# Carrier_Board.net
KiCad netlist of a schematic drawn in EAGLE
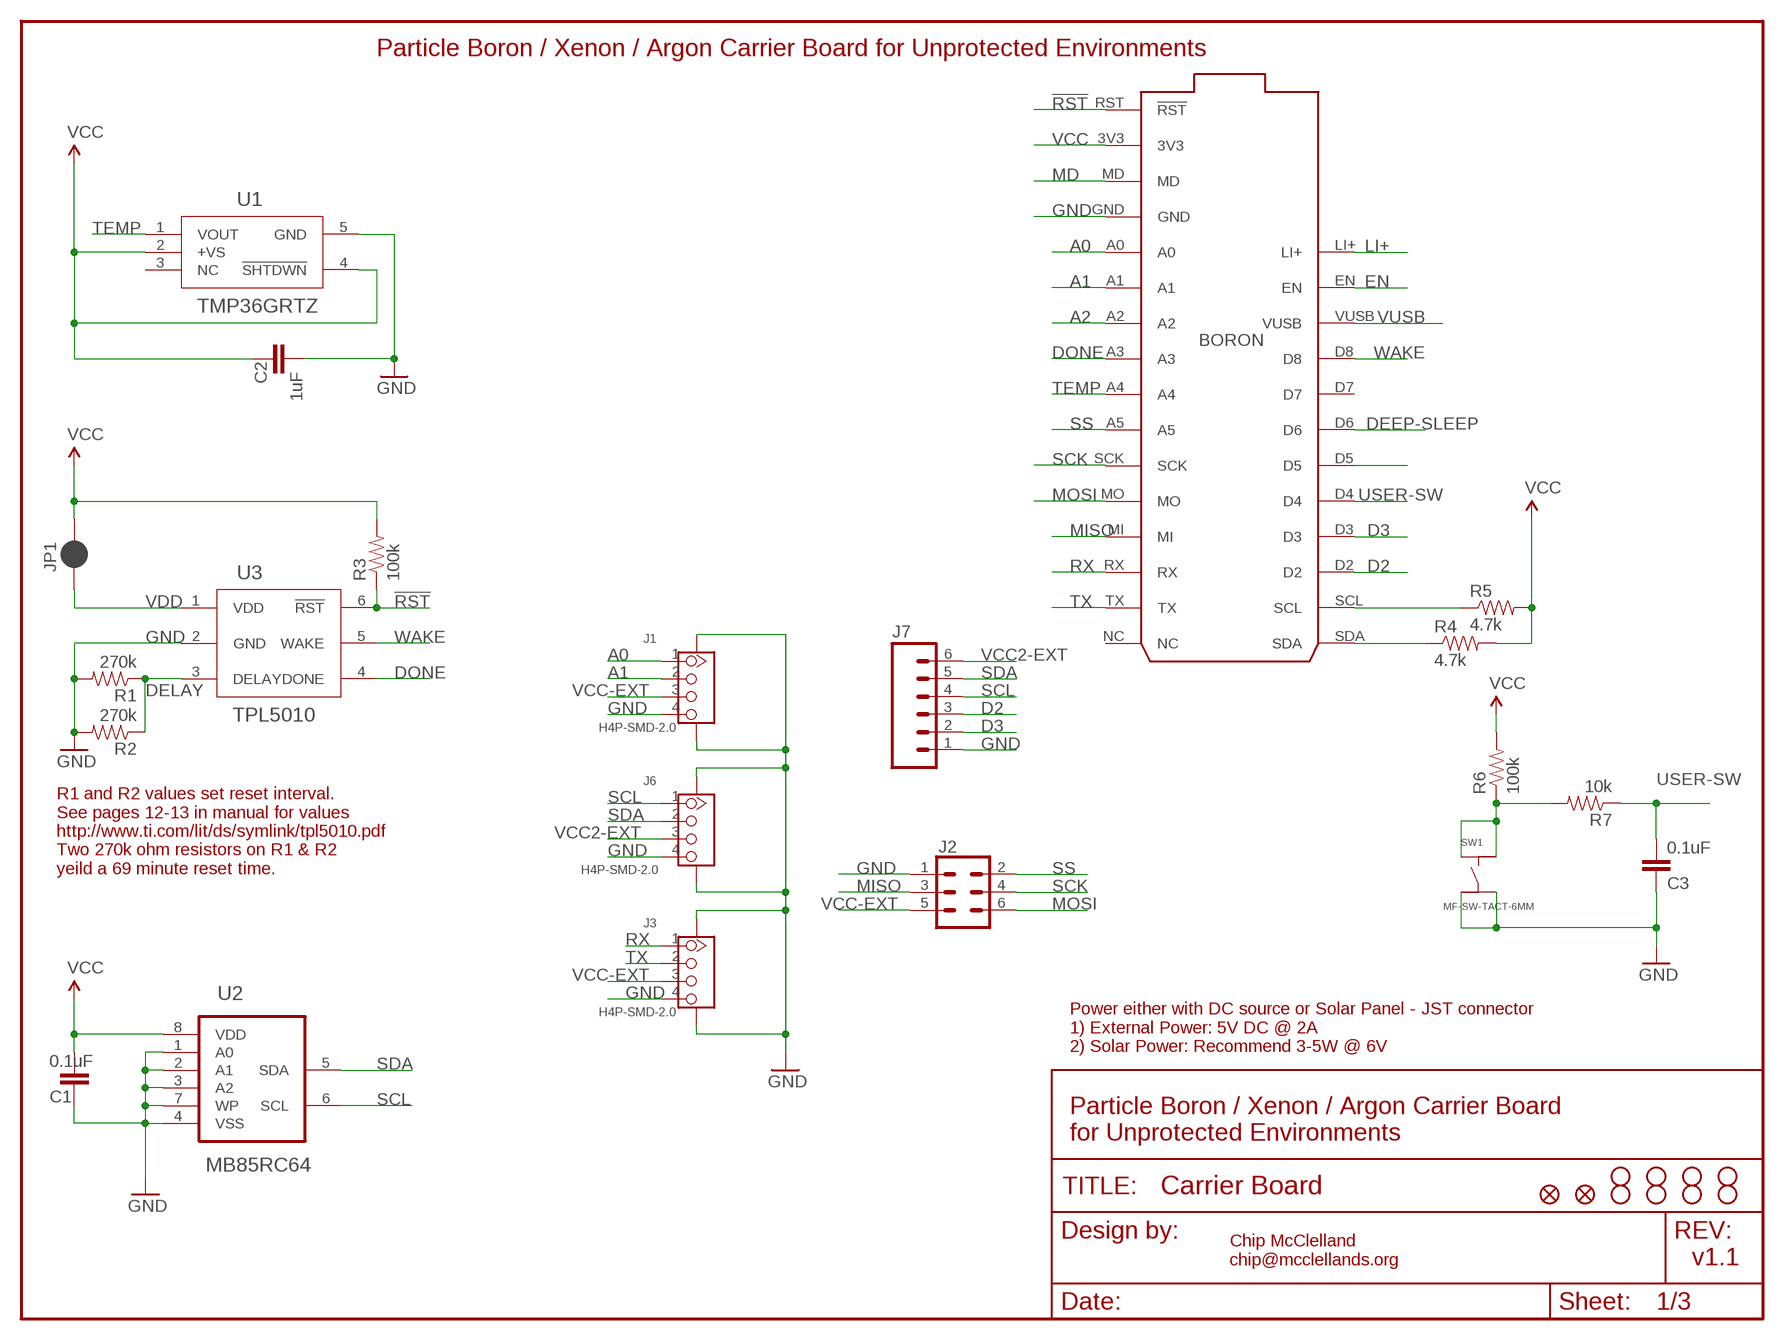
[diagram p0: schematic, sheet 1]
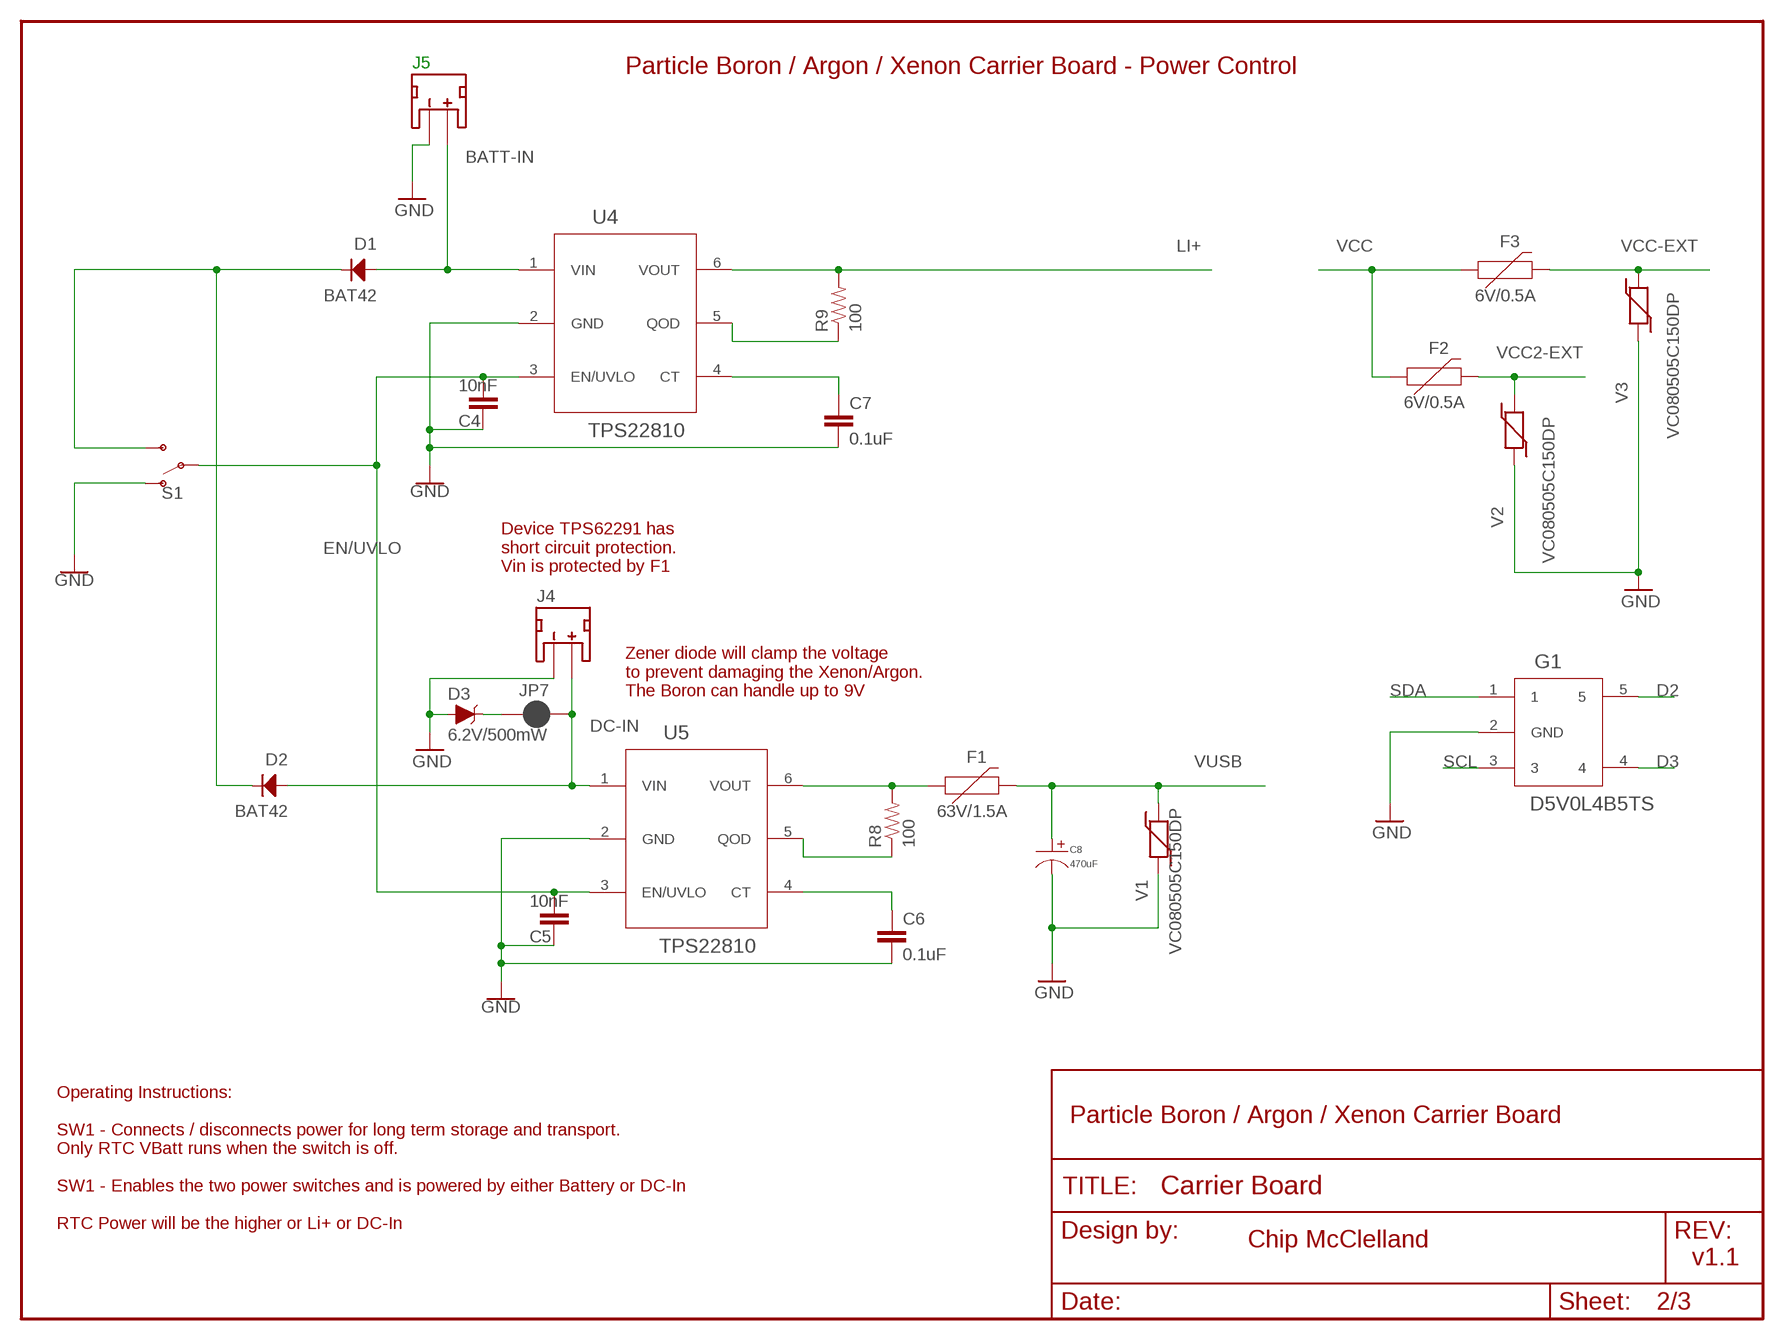
[diagram p1: schematic, sheet 2]
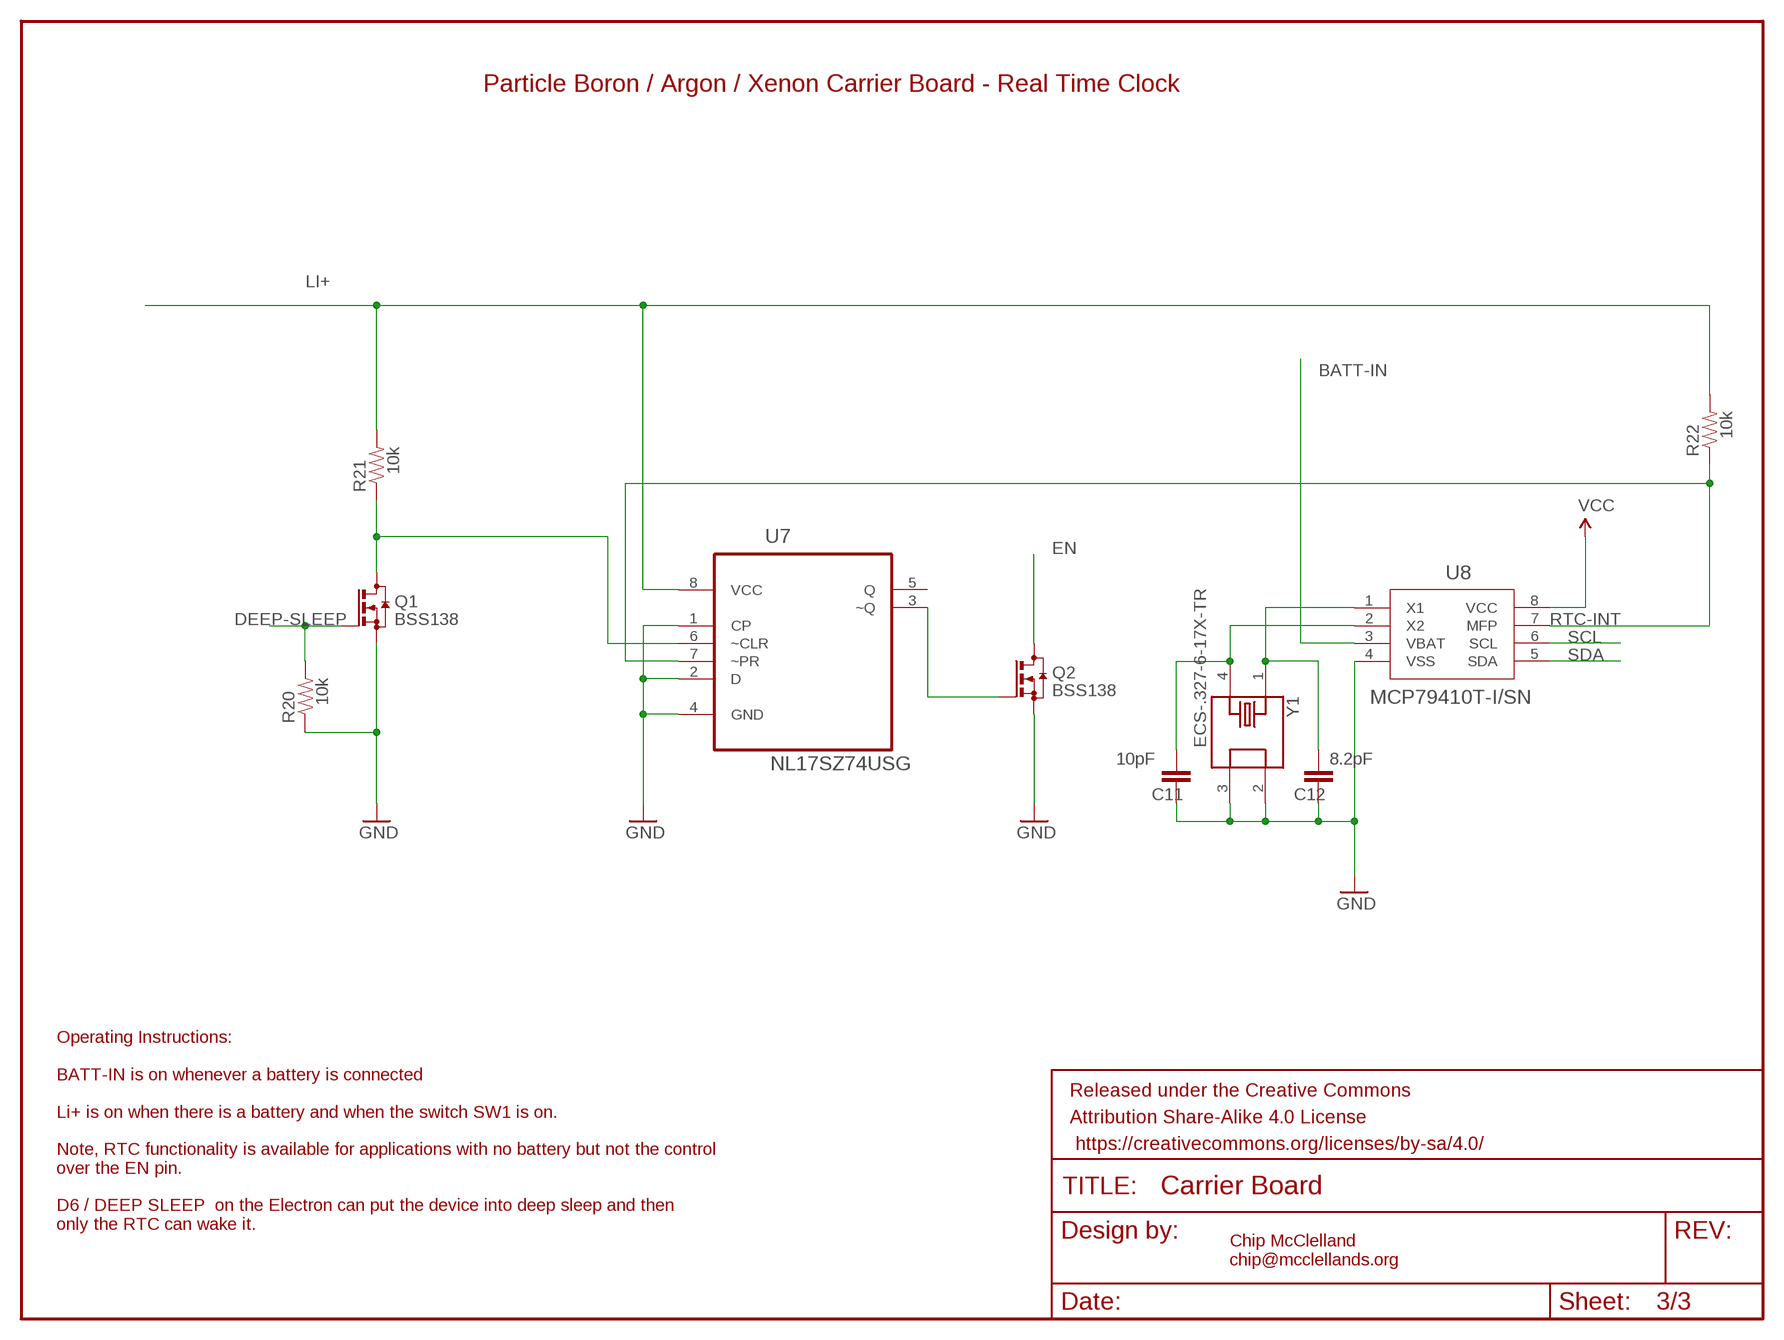
[diagram p2: schematic, sheet 3]

(export (version "E")
  (design (tool "Eeschema 10.0.6"))
  (components
    (comp (ref "C11")
      (value "10pF")
      (footprint "eagle-import:0805@1")
      (fields (field (name "HOUSEPART") "No") (field (name "MPN") "C0805C100JDGACTU‎"))
      (libsource (lib "eagle-import") (part "CAP0805"))
    )
    (comp (ref "C12")
      (value "8.2pF")
      (footprint "eagle-import:0805@1")
      (fields (field (name "HOUSEPART") "No") (field (name "MPN") "C0805C829D5GACTU‎"))
      (libsource (lib "eagle-import") (part "CAP0805"))
    )
    (comp (ref "FRAME3")
      (value "FRAME-LETTER")
      (footprint "eagle-import:CREATIVE_COMMONS")
      (fields (field (name "POPULATE") "0"))
      (libsource (lib "eagle-import") (part "SparkFun-Aesthetics_507_FRAME-LETTER"))
    )
    (comp (ref "Q1")
      (value "BSS138")
      (footprint "eagle-import:SOT23")
      (fields (field (name "HOUSEPART") "Yes") (field (name "MPN") "MF-DSC-SOT233-BSS138"))
      (libsource (lib "eagle-import") (part "BSS123"))
    )
    (comp (ref "Q2")
      (value "BSS138")
      (footprint "eagle-import:SOT23")
      (fields (field (name "HOUSEPART") "Yes") (field (name "MPN") "MF-DSC-SOT233-BSS138"))
      (libsource (lib "eagle-import") (part "BSS123"))
    )
    (comp (ref "R20")
      (value "10k")
      (footprint "eagle-import:0805")
      (fields (field (name "HOUSEPART") "YES") (field (name "MPN") "MF-RES-0805-10K"))
      (libsource (lib "eagle-import") (part "RESISTOR0805-RES"))
    )
    (comp (ref "R21")
      (value "10k")
      (footprint "eagle-import:0805")
      (fields (field (name "HOUSEPART") "YES") (field (name "MPN") "MF-RES-0805-10K"))
      (libsource (lib "eagle-import") (part "RESISTOR0805-RES"))
    )
    (comp (ref "R22")
      (value "10k")
      (footprint "eagle-import:0805")
      (fields (field (name "HOUSEPART") "YES") (field (name "MPN") "MF-RES-0805-10K"))
      (libsource (lib "eagle-import") (part "RESISTOR0805-RES"))
    )
    (comp (ref "U7")
      (value "NL17SZ74USG")
      (footprint "eagle-import:SOP50P310X90-8N")
      (fields
        (field (name "DIGI-KEY_PART_NUMBER") "NL17SZ74USGOSCT-ND")
        (field (name "MF") "ON Semiconductor")
      )
      (libsource (lib "eagle-import") (part "NL17SZ74USG"))
    )
    (comp (ref "U8")
      (value "MCP79410T-I/SN")
      (footprint "eagle-import:SOIC8-N_MC")
      (fields (field (name "MANUFACTURER_PART_NUMBER") "MCP79410TISN"))
      (libsource (lib "eagle-import") (part "MCP79410T-I/SN"))
    )
    (comp (ref "Y1")
      (value "ECS-.327-6-17X-TR")
      (footprint "eagle-import:XTAL_ECS-.327-6-17X-TR")
      (fields (field (name "DIGI-KEY_PART_NUMBER") "XC1307CT-ND") (field (name "MF") "ECS Inc."))
      (libsource (lib "eagle-import") (part "ECS-.327-6-17X-TR"))
    )
    (comp (ref "C4")
      (value "10nF")
      (footprint "eagle-import:0805@1")
      (fields (field (name "HOUSEPART") "No") (field (name "MPN") "08051C103K4T2A"))
      (libsource (lib "eagle-import") (part "CAP0805"))
    )
    (comp (ref "C5")
      (value "10nF")
      (footprint "eagle-import:0805@1")
      (fields (field (name "HOUSEPART") "No") (field (name "MPN") "08051C103K4T2A"))
      (libsource (lib "eagle-import") (part "CAP0805"))
    )
    (comp (ref "C6")
      (value "0.1uF")
      (footprint "eagle-import:0805@1")
      (fields (field (name "HOUSEPART") "Yes") (field (name "MPN") "MF-CAP-0805-0.1uF"))
      (libsource (lib "eagle-import") (part "CAP0805"))
    )
    (comp (ref "C7")
      (value "0.1uF")
      (footprint "eagle-import:0805@1")
      (fields (field (name "HOUSEPART") "Yes") (field (name "MPN") "MF-CAP-0805-0.1uF"))
      (libsource (lib "eagle-import") (part "CAP0805"))
    )
    (comp (ref "C8")
      (value "470uF")
      (footprint "eagle-import:CP10MM")
      (fields (field (name "HOUSEPART") "1") (field (name "MPN") "MF-CAP-10MM-470uF"))
      (libsource (lib "eagle-import") (part "CAPACITOR_P_10MM"))
    )
    (comp (ref "D1")
      (value "BAT42")
      (footprint "eagle-import:SOD-123")
      (fields (field (name "HOUSEPART") "YES") (field (name "MPN") "MF-DIO-SOD123-BAT42"))
      (libsource (lib "eagle-import") (part "DIODES_SOD-123_BAT42"))
    )
    (comp (ref "D2")
      (value "BAT42")
      (footprint "eagle-import:SOD-123")
      (fields (field (name "HOUSEPART") "YES") (field (name "MPN") "MF-DIO-SOD123-BAT42"))
      (libsource (lib "eagle-import") (part "DIODES_SOD-123_BAT42"))
    )
    (comp (ref "D3")
      (value "6.2V/500mW")
      (footprint "eagle-import:PANASONIC_SMINI2-F5-B")
      (fields (field (name "MPN") "TDZ6V2J,115"))
      (libsource (lib "eagle-import") (part "DIODE-ZENER-DZ2J150M0L"))
    )
    (comp (ref "F1")
      (value "63V/1.5A")
      (footprint "eagle-import:1206")
      (fields (field (name "MPN") "046801.5NR"))
      (libsource (lib "eagle-import") (part "PPTC_HALF-AMP"))
    )
    (comp (ref "F2")
      (value "6V/0.5A")
      (footprint "eagle-import:1206")
      (fields (field (name "MPN") "0466.500NR"))
      (libsource (lib "eagle-import") (part "PPTC_HALF-AMP"))
    )
    (comp (ref "F3")
      (value "6V/0.5A")
      (footprint "eagle-import:1206")
      (fields (field (name "MPN") "0466.500NR"))
      (libsource (lib "eagle-import") (part "PPTC_HALF-AMP"))
    )
    (comp (ref "FRAME2")
      (value "FRAME-LETTER")
      (footprint "eagle-import:CREATIVE_COMMONS")
      (fields (field (name "POPULATE") "0"))
      (libsource (lib "eagle-import") (part "FRAME-LETTER"))
    )
    (comp (ref "G1")
      (value "D5V0L4B5TS")
      (footprint "eagle-import:SOT-23-5")
      (fields (field (name "MPN") "D5V0L4B5TS-7"))
      (libsource (lib "eagle-import") (part "D5V0L4B5TS"))
    )
    (comp (ref "J4")
      (value "S2B-PH-SM4-TB(LF)(SN)")
      (footprint "eagle-import:JST-2-SMD")
      (fields (field (name "MFG") "JST S2B-PH-SM4-TB(LF)(SN)"))
      (libsource (lib "eagle-import") (part "JST_2MM_MALE"))
    )
    (comp (ref "J5")
      (value "S2B-PH-SM4-TB(LF)(SN)")
      (footprint "eagle-import:JST-2-SMD")
      (fields (field (name "MFG") "JST S2B-PH-SM4-TB(LF)(SN)"))
      (libsource (lib "eagle-import") (part "JST_2MM_MALE"))
    )
    (comp (ref "JP7")
      (value "JUMPER-SMT_2_NC_PASTE_SILK")
      (footprint "eagle-import:SMT-JUMPER_2_NC_PASTE_SILK")
      (libsource (lib "eagle-import") (part "JUMPER-SMT_2_NC_PASTE_SILK"))
    )
    (comp (ref "R8")
      (value "100")
      (footprint "eagle-import:0805")
      (fields (field (name "HOUSEPART") "Yes") (field (name "MPN") "MF-RES-0805-100"))
      (libsource (lib "eagle-import") (part "RESISTOR0805-RES"))
    )
    (comp (ref "R9")
      (value "100")
      (footprint "eagle-import:0805")
      (fields (field (name "HOUSEPART") "Yes") (field (name "MPN") "MF-RES-0805-100"))
      (libsource (lib "eagle-import") (part "RESISTOR0805-RES"))
    )
    (comp (ref "S1")
      (value "SWITCH-SPDT-SMD-AYZ0202")
      (footprint "eagle-import:SWITCH_DPDT_SMD_AYZ0202")
      (fields (field (name "MPN") "AYZ0202AGRLC"))
      (libsource (lib "eagle-import") (part "SWITCH-SPDT-SMD-AYZ0202"))
    )
    (comp (ref "U4")
      (value "TPS22810")
      (footprint "eagle-import:SOT-23-6")
      (fields (field (name "MPN") "TPS22810DBVT"))
      (libsource (lib "eagle-import") (part "TPS22810"))
    )
    (comp (ref "U5")
      (value "TPS22810")
      (footprint "eagle-import:SOT-23-6")
      (fields (field (name "MPN") "TPS22810DBVT"))
      (libsource (lib "eagle-import") (part "TPS22810"))
    )
    (comp (ref "V1")
      (value "VC080505C150DP")
      (footprint "eagle-import:0805")
      (libsource (lib "eagle-import") (part "VARISTOR"))
    )
    (comp (ref "V2")
      (value "VC080505C150DP")
      (footprint "eagle-import:0805")
      (libsource (lib "eagle-import") (part "VARISTOR"))
    )
    (comp (ref "V3")
      (value "VC080505C150DP")
      (footprint "eagle-import:0805")
      (libsource (lib "eagle-import") (part "VARISTOR"))
    )
    (comp (ref "C1")
      (value "0.1uF")
      (footprint "eagle-import:0805@1")
      (fields (field (name "HOUSEPART") "YES") (field (name "MPN") "MF-CAP-0805-0.1uF"))
      (libsource (lib "eagle-import") (part "CAP0805"))
    )
    (comp (ref "C2")
      (value "1uF")
      (footprint "eagle-import:0805@1")
      (fields (field (name "MPN") "MF-CAP-0805-1uF"))
      (libsource (lib "eagle-import") (part "CAP0805"))
    )
    (comp (ref "C3")
      (value "0.1uF")
      (footprint "eagle-import:0805@1")
      (fields (field (name "MPN") "MF-CAP-0805-0.1uF"))
      (libsource (lib "eagle-import") (part "CAP0805"))
    )
    (comp (ref "FD1")
      (value "FIDUCIALUFIDUCIAL")
      (footprint "eagle-import:FIDUCIAL-MICRO")
      (libsource (lib "eagle-import") (part "FIDUCIALUFIDUCIAL"))
    )
    (comp (ref "FD2")
      (value "FIDUCIALUFIDUCIAL")
      (footprint "eagle-import:FIDUCIAL-MICRO")
      (libsource (lib "eagle-import") (part "FIDUCIALUFIDUCIAL"))
    )
    (comp (ref "FRAME1")
      (value "FRAME-LETTER")
      (footprint "eagle-import:CREATIVE_COMMONS")
      (fields (field (name "POPULATE") "0"))
      (libsource (lib "eagle-import") (part "FRAME-LETTER"))
    )
    (comp (ref "H1")
      (value "STAND-OFF-M2.5")
      (footprint "eagle-import:STAND-OFF-M2.5")
      (libsource (lib "eagle-import") (part "STAND-OFF-M2.5"))
    )
    (comp (ref "H2")
      (value "STAND-OFF-M2.5")
      (footprint "eagle-import:STAND-OFF-M2.5")
      (libsource (lib "eagle-import") (part "STAND-OFF-M2.5"))
    )
    (comp (ref "H3")
      (value "STAND-OFF-M2.5")
      (footprint "eagle-import:STAND-OFF-M2.5")
      (libsource (lib "eagle-import") (part "STAND-OFF-M2.5"))
    )
    (comp (ref "H4")
      (value "STAND-OFF-M2.5")
      (footprint "eagle-import:STAND-OFF-M2.5")
      (libsource (lib "eagle-import") (part "STAND-OFF-M2.5"))
    )
    (comp (ref "J1")
      (value "H4P-SMD-2.0")
      (footprint "eagle-import:HW4-SMD-2.0")
      (fields (field (name "MPN") "B4B-PH-SM4-TB(LF)(SN)"))
      (libsource (lib "eagle-import") (part "GROVE-CONNECTOR-SMD(4+2P-2.0)"))
    )
    (comp (ref "J2")
      (value "CONN_03X22X3_SILK_MALE_PTH")
      (footprint "eagle-import:2X3")
      (libsource (lib "eagle-import") (part "CONN_03X22X3_SILK_MALE_PTH"))
    )
    (comp (ref "J3")
      (value "H4P-SMD-2.0")
      (footprint "eagle-import:HW4-SMD-2.0")
      (fields (field (name "MPN") "B4B-PH-SM4-TB(LF)(SN)"))
      (libsource (lib "eagle-import") (part "GROVE-CONNECTOR-SMD(4+2P-2.0)"))
    )
    (comp (ref "J6")
      (value "H4P-SMD-2.0")
      (footprint "eagle-import:HW4-SMD-2.0")
      (fields (field (name "MPN") "B4B-PH-SM4-TB(LF)(SN)"))
      (libsource (lib "eagle-import") (part "GROVE-CONNECTOR-SMD(4+2P-2.0)"))
    )
    (comp (ref "J7")
      (value "M06LOCK")
      (footprint "eagle-import:1X06_LOCK")
      (libsource (lib "eagle-import") (part "M06LOCK"))
    )
    (comp (ref "JP1")
      (value "JUMPER-SMT_2_NC_PASTE_SILK")
      (footprint "eagle-import:SMT-JUMPER_2_NC_PASTE_SILK")
      (libsource (lib "eagle-import") (part "JUMPER-SMT_2_NC_PASTE_SILK"))
    )
    (comp (ref "JP3")
      (value "STAND-OFF")
      (footprint "eagle-import:STAND-OFF")
      (libsource (lib "eagle-import") (part "STAND-OFF"))
    )
    (comp (ref "JP4")
      (value "STAND-OFF")
      (footprint "eagle-import:STAND-OFF")
      (libsource (lib "eagle-import") (part "STAND-OFF"))
    )
    (comp (ref "JP5")
      (value "STAND-OFF")
      (footprint "eagle-import:STAND-OFF")
      (libsource (lib "eagle-import") (part "STAND-OFF"))
    )
    (comp (ref "JP6")
      (value "STAND-OFF")
      (footprint "eagle-import:STAND-OFF")
      (libsource (lib "eagle-import") (part "STAND-OFF"))
    )
    (comp (ref "P1")
      (value "PARTICLE-DEVICES-BORON")
      (footprint "eagle-import:PARTICLE-DEVICES_BORON")
      (libsource (lib "eagle-import") (part "PARTICLE-DEVICES-BORON"))
    )
    (comp (ref "R1")
      (value "270k")
      (footprint "eagle-import:0805")
      (fields (field (name "MPN") "ERJ-P06F2703V"))
      (libsource (lib "eagle-import") (part "RESISTOR0805-RES"))
    )
    (comp (ref "R2")
      (value "270k")
      (footprint "eagle-import:0805")
      (fields (field (name "MPN") "ERJ-P06F2703V"))
      (libsource (lib "eagle-import") (part "RESISTOR0805-RES"))
    )
    (comp (ref "R3")
      (value "100k")
      (footprint "eagle-import:0805")
      (fields (field (name "HOUSEPART") "YES") (field (name "MPN") "MF-RES-0805-100K"))
      (libsource (lib "eagle-import") (part "RESISTOR0805-RES"))
    )
    (comp (ref "R4")
      (value "4.7k")
      (footprint "eagle-import:0805")
      (fields (field (name "MPN") "MF-RES-0805-4.7K"))
      (libsource (lib "eagle-import") (part "RESISTOR0805-RES"))
    )
    (comp (ref "R5")
      (value "4.7k")
      (footprint "eagle-import:0805")
      (fields (field (name "MPN") "MF-RES-0805-4.7K"))
      (libsource (lib "eagle-import") (part "RESISTOR0805-RES"))
    )
    (comp (ref "R6")
      (value "100k")
      (footprint "eagle-import:0805")
      (fields (field (name "HOUSEPART") "YES") (field (name "MPN") "MF-RES-0805-100K"))
      (libsource (lib "eagle-import") (part "RESISTOR0805-RES"))
    )
    (comp (ref "R7")
      (value "10k")
      (footprint "eagle-import:0805")
      (fields (field (name "HOUSEPART") "YES") (field (name "MPN") "MF-RES-0805-10K"))
      (libsource (lib "eagle-import") (part "RESISTOR0805-RES"))
    )
    (comp (ref "SW1")
      (value "MF-SW-TACT-6MM")
      (footprint "eagle-import:TACT6MM")
      (fields (field (name "HOUSEPART") "YES"))
      (libsource (lib "eagle-import") (part "TACT_6MM"))
    )
    (comp (ref "U1")
      (value "TMP36GRTZ")
      (footprint "eagle-import:RJ_5")
      (fields
        (field (name "MANUFACTURER_PART_NUMBER") "TMP36GRTZREEL7")
        (field (name "MANUFACTURER_PART_NUMBER_1") "TMP36GRTZ-REEL7")
        (field (name "MPN") "TMP36GRTZ-REEL7")
      )
      (libsource (lib "eagle-import") (part "TMP36GRTZ-REEL7"))
    )
    (comp (ref "U2")
      (value "MB85RC64")
      (footprint "eagle-import:SOIC127P600X175-8N")
      (fields (field (name "MPN") "MB85RC128PNF-G-JNE1") (field (name "MPN_1") "MB85RC64PNF-G-JNE1"))
      (libsource (lib "eagle-import") (part "MB85RC128PNF-G-JNE1"))
    )
    (comp (ref "U3")
      (value "TPL5010")
      (footprint "eagle-import:TSOT-23")
      (fields (field (name "MPN") "TPL5010DDCR"))
      (libsource (lib "eagle-import") (part "TPL5010"))
    )
  )
  (nets
    (net (code "1") (name "A0") (class "Default")
      (node (ref "J1") (pin "1") (pinfunction "1_1") (pintype "bidirectional"))
      (node (ref "P1") (pin "A0") (pinfunction "A0_A0") (pintype "bidirectional"))
    )
    (net (code "2") (name "A1") (class "Default")
      (node (ref "J1") (pin "2") (pinfunction "2_2") (pintype "bidirectional"))
      (node (ref "P1") (pin "A1") (pinfunction "A1_A1") (pintype "bidirectional"))
    )
    (net (code "3") (name "A2") (class "Default")
      (node (ref "P1") (pin "A2") (pinfunction "A2_A2") (pintype "bidirectional"))
    )
    (net (code "4") (name "BATT-IN") (class "Default")
      (node (ref "D1") (pin "ANODE") (pinfunction "ANODE_ANODE") (pintype "bidirectional"))
      (node (ref "J5") (pin "2") (pinfunction "+_2") (pintype "bidirectional"))
      (node (ref "U4") (pin "1") (pinfunction "VIN_1") (pintype "power_in"))
      (node (ref "U8") (pin "3") (pinfunction "VBAT_3") (pintype "input"))
    )
    (net (code "5") (name "D2") (class "Default")
      (node (ref "G1") (pin "5") (pinfunction "5_5") (pintype "output"))
      (node (ref "J7") (pin "3") (pinfunction "3_3") (pintype "passive"))
      (node (ref "P1") (pin "D2") (pinfunction "D2_D2") (pintype "bidirectional"))
    )
    (net (code "6") (name "D3") (class "Default")
      (node (ref "G1") (pin "4") (pinfunction "4_4") (pintype "output"))
      (node (ref "J7") (pin "2") (pinfunction "2_2") (pintype "passive"))
      (node (ref "P1") (pin "D3") (pinfunction "D3_D3") (pintype "bidirectional"))
    )
    (net (code "7") (name "DC-IN") (class "Default")
      (node (ref "D2") (pin "ANODE") (pinfunction "ANODE_ANODE") (pintype "bidirectional"))
      (node (ref "J4") (pin "2") (pinfunction "+_2") (pintype "bidirectional"))
      (node (ref "JP7") (pin "1") (pinfunction "1_1") (pintype "passive"))
      (node (ref "U5") (pin "1") (pinfunction "VIN_1") (pintype "power_in"))
    )
    (net (code "8") (name "DEEP-SLEEP") (class "Default")
      (node (ref "P1") (pin "D6") (pinfunction "D6_D6") (pintype "bidirectional"))
      (node (ref "Q1") (pin "1") (pinfunction "G_1") (pintype "passive"))
      (node (ref "R20") (pin "2") (pinfunction "2_2") (pintype "passive"))
    )
    (net (code "9") (name "DELAY") (class "Default")
      (node (ref "R1") (pin "1") (pinfunction "1_1") (pintype "passive"))
      (node (ref "R2") (pin "1") (pinfunction "1_1") (pintype "passive"))
      (node (ref "U3") (pin "3") (pinfunction "DELAY_3") (pintype "input"))
    )
    (net (code "10") (name "DONE") (class "Default")
      (node (ref "P1") (pin "A3") (pinfunction "A3_A3") (pintype "bidirectional"))
      (node (ref "U3") (pin "4") (pinfunction "DONE_4") (pintype "input"))
    )
    (net (code "11") (name "EN") (class "Default")
      (node (ref "P1") (pin "EN") (pinfunction "EN_EN") (pintype "bidirectional"))
      (node (ref "Q2") (pin "3") (pinfunction "D_3") (pintype "passive"))
    )
    (net (code "12") (name "EN{slash}UVLO") (class "Default")
      (node (ref "C4") (pin "1") (pinfunction "1_1") (pintype "passive"))
      (node (ref "C5") (pin "1") (pinfunction "1_1") (pintype "passive"))
      (node (ref "S1") (pin "2") (pinfunction "P_2") (pintype "passive"))
      (node (ref "U4") (pin "3") (pinfunction "EN/UVLO_3") (pintype "input"))
      (node (ref "U5") (pin "3") (pinfunction "EN/UVLO_3") (pintype "input"))
    )
    (net (code "13") (name "GND") (class "Default")
      (node (ref "C1") (pin "2") (pinfunction "2_2") (pintype "passive"))
      (node (ref "C11") (pin "2") (pinfunction "2_2") (pintype "passive"))
      (node (ref "C12") (pin "2") (pinfunction "2_2") (pintype "passive"))
      (node (ref "C2") (pin "2") (pinfunction "2_2") (pintype "passive"))
      (node (ref "C3") (pin "2") (pinfunction "2_2") (pintype "passive"))
      (node (ref "C4") (pin "2") (pinfunction "2_2") (pintype "passive"))
      (node (ref "C5") (pin "2") (pinfunction "2_2") (pintype "passive"))
      (node (ref "C6") (pin "2") (pinfunction "2_2") (pintype "passive"))
      (node (ref "C7") (pin "2") (pinfunction "2_2") (pintype "passive"))
      (node (ref "C8") (pin "P$2") (pinfunction "P$2_P$2") (pintype "passive"))
      (node (ref "D3") (pin "A") (pinfunction "A_A") (pintype "passive"))
      (node (ref "G1") (pin "2") (pinfunction "GND_2") (pintype "power_in"))
      (node (ref "J1") (pin "4") (pinfunction "4_4") (pintype "bidirectional"))
      (node (ref "J1") (pin "SS1") (pinfunction "SS1_SS1") (pintype "bidirectional"))
      (node (ref "J1") (pin "SS2") (pinfunction "SS2_SS2") (pintype "bidirectional"))
      (node (ref "J2") (pin "1") (pinfunction "1_1") (pintype "bidirectional"))
      (node (ref "J3") (pin "4") (pinfunction "4_4") (pintype "bidirectional"))
      (node (ref "J3") (pin "SS1") (pinfunction "SS1_SS1") (pintype "bidirectional"))
      (node (ref "J3") (pin "SS2") (pinfunction "SS2_SS2") (pintype "bidirectional"))
      (node (ref "J4") (pin "1") (pinfunction "-_1") (pintype "bidirectional"))
      (node (ref "J5") (pin "1") (pinfunction "-_1") (pintype "bidirectional"))
      (node (ref "J6") (pin "4") (pinfunction "4_4") (pintype "bidirectional"))
      (node (ref "J6") (pin "SS1") (pinfunction "SS1_SS1") (pintype "bidirectional"))
      (node (ref "J6") (pin "SS2") (pinfunction "SS2_SS2") (pintype "bidirectional"))
      (node (ref "J7") (pin "1") (pinfunction "1_1") (pintype "passive"))
      (node (ref "P1") (pin "GND") (pinfunction "GND_GND") (pintype "bidirectional"))
      (node (ref "Q1") (pin "2") (pinfunction "S_2") (pintype "passive"))
      (node (ref "Q2") (pin "2") (pinfunction "S_2") (pintype "passive"))
      (node (ref "R1") (pin "2") (pinfunction "2_2") (pintype "passive"))
      (node (ref "R2") (pin "2") (pinfunction "2_2") (pintype "passive"))
      (node (ref "R20") (pin "1") (pinfunction "1_1") (pintype "passive"))
      (node (ref "S1") (pin "1") (pinfunction "O_1") (pintype "passive"))
      (node (ref "SW1") (pin "P$3") (pinfunction "P$3_P$3") (pintype "bidirectional"))
      (node (ref "SW1") (pin "P$4") (pinfunction "P$4_P$4") (pintype "bidirectional"))
      (node (ref "U1") (pin "5") (pinfunction "GND_5") (pintype "passive"))
      (node (ref "U2") (pin "1") (pinfunction "A0_1") (pintype "input"))
      (node (ref "U2") (pin "2") (pinfunction "A1_2") (pintype "input"))
      (node (ref "U2") (pin "3") (pinfunction "A2_3") (pintype "input"))
      (node (ref "U2") (pin "4") (pinfunction "VSS_4") (pintype "passive"))
      (node (ref "U2") (pin "7") (pinfunction "WP_7") (pintype "input"))
      (node (ref "U3") (pin "2") (pinfunction "GND_2") (pintype "power_in"))
      (node (ref "U4") (pin "2") (pinfunction "GND_2") (pintype "power_in"))
      (node (ref "U5") (pin "2") (pinfunction "GND_2") (pintype "power_in"))
      (node (ref "U7") (pin "1") (pinfunction "CP_1") (pintype "input"))
      (node (ref "U7") (pin "2") (pinfunction "D_2") (pintype "input"))
      (node (ref "U7") (pin "4") (pinfunction "GND_4") (pintype "passive"))
      (node (ref "U8") (pin "4") (pinfunction "VSS_4") (pintype "power_in"))
      (node (ref "V1") (pin "1") (pinfunction "1_1") (pintype "passive"))
      (node (ref "V2") (pin "1") (pinfunction "1_1") (pintype "passive"))
      (node (ref "V3") (pin "1") (pinfunction "1_1") (pintype "passive"))
      (node (ref "Y1") (pin "2") (pinfunction "2_2") (pintype "passive"))
      (node (ref "Y1") (pin "3") (pinfunction "3_3") (pintype "passive"))
    )
    (net (code "14") (name "LI+") (class "Default")
      (node (ref "P1") (pin "LI+") (pinfunction "LI+_LI+") (pintype "bidirectional"))
      (node (ref "R21") (pin "2") (pinfunction "2_2") (pintype "passive"))
      (node (ref "R22") (pin "2") (pinfunction "2_2") (pintype "passive"))
      (node (ref "R9") (pin "2") (pinfunction "2_2") (pintype "passive"))
      (node (ref "U4") (pin "6") (pinfunction "VOUT_6") (pintype "power_in"))
      (node (ref "U7") (pin "8") (pinfunction "VCC_8") (pintype "power_in"))
    )
    (net (code "15") (name "MD") (class "Default")
      (node (ref "P1") (pin "MD") (pinfunction "MD_MD") (pintype "bidirectional"))
    )
    (net (code "16") (name "MISO") (class "Default")
      (node (ref "J2") (pin "3") (pinfunction "3_3") (pintype "bidirectional"))
      (node (ref "P1") (pin "MI") (pinfunction "MI_MI") (pintype "bidirectional"))
    )
    (net (code "17") (name "MOSI") (class "Default")
      (node (ref "J2") (pin "6") (pinfunction "6_6") (pintype "bidirectional"))
      (node (ref "P1") (pin "MO") (pinfunction "MO_MO") (pintype "bidirectional"))
    )
    (net (code "18") (name "Net-(D3-PadC)") (class "Default")
      (node (ref "D3") (pin "C") (pinfunction "C_C") (pintype "passive"))
      (node (ref "JP7") (pin "2") (pinfunction "2_2") (pintype "passive"))
    )
    (net (code "19") (name "Net-(Q1-D)") (class "Default")
      (node (ref "Q1") (pin "3") (pinfunction "D_3") (pintype "passive"))
      (node (ref "R21") (pin "1") (pinfunction "1_1") (pintype "passive"))
      (node (ref "U7") (pin "6") (pinfunction "~{CLR}_6") (pintype "input"))
    )
    (net (code "20") (name "Net-(Q2-G)") (class "Default")
      (node (ref "Q2") (pin "1") (pinfunction "G_1") (pintype "passive"))
      (node (ref "U7") (pin "3") (pinfunction "~{Q}_3") (pintype "output"))
    )
    (net (code "21") (name "Net-(R6-Pad1)") (class "Default")
      (node (ref "R6") (pin "1") (pinfunction "1_1") (pintype "passive"))
      (node (ref "R7") (pin "2") (pinfunction "2_2") (pintype "passive"))
      (node (ref "SW1") (pin "P$1") (pinfunction "P$1_P$1") (pintype "bidirectional"))
      (node (ref "SW1") (pin "P$2") (pinfunction "P$2_P$2") (pintype "bidirectional"))
    )
    (net (code "22") (name "Net-(S1-S)") (class "Default")
      (node (ref "D1") (pin "CATHODE") (pinfunction "CATHODE_CATHODE") (pintype "bidirectional"))
      (node (ref "D2") (pin "CATHODE") (pinfunction "CATHODE_CATHODE") (pintype "bidirectional"))
      (node (ref "S1") (pin "3") (pinfunction "S_3") (pintype "passive"))
    )
    (net (code "23") (name "Net-(U4-CT)") (class "Default")
      (node (ref "C7") (pin "1") (pinfunction "1_1") (pintype "passive"))
      (node (ref "U4") (pin "4") (pinfunction "CT_4") (pintype "bidirectional"))
    )
    (net (code "24") (name "Net-(U4-QOD)") (class "Default")
      (node (ref "R9") (pin "1") (pinfunction "1_1") (pintype "passive"))
      (node (ref "U4") (pin "5") (pinfunction "QOD_5") (pintype "bidirectional"))
    )
    (net (code "25") (name "Net-(U5-CT)") (class "Default")
      (node (ref "C6") (pin "1") (pinfunction "1_1") (pintype "passive"))
      (node (ref "U5") (pin "4") (pinfunction "CT_4") (pintype "bidirectional"))
    )
    (net (code "26") (name "Net-(U5-QOD)") (class "Default")
      (node (ref "R8") (pin "1") (pinfunction "1_1") (pintype "passive"))
      (node (ref "U5") (pin "5") (pinfunction "QOD_5") (pintype "bidirectional"))
    )
    (net (code "27") (name "Net-(U5-VOUT)") (class "Default")
      (node (ref "F1") (pin "1") (pinfunction "1_1") (pintype "bidirectional"))
      (node (ref "R8") (pin "2") (pinfunction "2_2") (pintype "passive"))
      (node (ref "U5") (pin "6") (pinfunction "VOUT_6") (pintype "power_in"))
    )
    (net (code "28") (name "Net-(U8-X1)") (class "Default")
      (node (ref "C12") (pin "1") (pinfunction "1_1") (pintype "passive"))
      (node (ref "U8") (pin "1") (pinfunction "X1_1") (pintype "input"))
      (node (ref "Y1") (pin "1") (pinfunction "1_1") (pintype "passive"))
    )
    (net (code "29") (name "Net-(U8-X2)") (class "Default")
      (node (ref "C11") (pin "1") (pinfunction "1_1") (pintype "passive"))
      (node (ref "U8") (pin "2") (pinfunction "X2_2") (pintype "output"))
      (node (ref "Y1") (pin "4") (pinfunction "4_4") (pintype "passive"))
    )
    (net (code "30") (name "RTC-INT") (class "Default")
      (node (ref "R22") (pin "1") (pinfunction "1_1") (pintype "passive"))
      (node (ref "U7") (pin "7") (pinfunction "~{PR}_7") (pintype "input"))
      (node (ref "U8") (pin "7") (pinfunction "MFP_7") (pintype "passive"))
    )
    (net (code "31") (name "RX") (class "Default")
      (node (ref "J3") (pin "1") (pinfunction "1_1") (pintype "bidirectional"))
      (node (ref "P1") (pin "RX") (pinfunction "RX_RX") (pintype "bidirectional"))
    )
    (net (code "32") (name "SCK") (class "Default")
      (node (ref "J2") (pin "4") (pinfunction "4_4") (pintype "bidirectional"))
      (node (ref "P1") (pin "SCK") (pinfunction "SCK_SCK") (pintype "bidirectional"))
    )
    (net (code "33") (name "SCL") (class "Default")
      (node (ref "G1") (pin "3") (pinfunction "3_3") (pintype "input"))
      (node (ref "J6") (pin "1") (pinfunction "1_1") (pintype "bidirectional"))
      (node (ref "J7") (pin "4") (pinfunction "4_4") (pintype "passive"))
      (node (ref "P1") (pin "SCL") (pinfunction "SCL_SCL") (pintype "bidirectional"))
      (node (ref "R5") (pin "1") (pinfunction "1_1") (pintype "passive"))
      (node (ref "U2") (pin "6") (pinfunction "SCL_6") (pintype "input"))
      (node (ref "U8") (pin "6") (pinfunction "SCL_6") (pintype "input"))
    )
    (net (code "34") (name "SDA") (class "Default")
      (node (ref "G1") (pin "1") (pinfunction "1_1") (pintype "input"))
      (node (ref "J6") (pin "2") (pinfunction "2_2") (pintype "bidirectional"))
      (node (ref "J7") (pin "5") (pinfunction "5_5") (pintype "passive"))
      (node (ref "P1") (pin "SDA") (pinfunction "SDA_SDA") (pintype "bidirectional"))
      (node (ref "R4") (pin "1") (pinfunction "1_1") (pintype "passive"))
      (node (ref "U2") (pin "5") (pinfunction "SDA_5") (pintype "bidirectional"))
      (node (ref "U8") (pin "5") (pinfunction "SDA_5") (pintype "bidirectional"))
    )
    (net (code "35") (name "SS") (class "Default")
      (node (ref "J2") (pin "2") (pinfunction "2_2") (pintype "bidirectional"))
      (node (ref "P1") (pin "A5") (pinfunction "A5_A5") (pintype "bidirectional"))
    )
    (net (code "36") (name "TEMP") (class "Default")
      (node (ref "P1") (pin "A4") (pinfunction "A4_A4") (pintype "bidirectional"))
      (node (ref "U1") (pin "1") (pinfunction "VOUT_1") (pintype "passive"))
    )
    (net (code "37") (name "TX") (class "Default")
      (node (ref "J3") (pin "2") (pinfunction "2_2") (pintype "bidirectional"))
      (node (ref "P1") (pin "TX") (pinfunction "TX_TX") (pintype "bidirectional"))
    )
    (net (code "38") (name "USER-SW") (class "Default")
      (node (ref "C3") (pin "1") (pinfunction "1_1") (pintype "passive"))
      (node (ref "P1") (pin "D4") (pinfunction "D4_D4") (pintype "bidirectional"))
      (node (ref "R7") (pin "1") (pinfunction "1_1") (pintype "passive"))
    )
    (net (code "39") (name "VCC") (class "Default")
      (node (ref "C1") (pin "1") (pinfunction "1_1") (pintype "passive"))
      (node (ref "C2") (pin "1") (pinfunction "1_1") (pintype "passive"))
      (node (ref "F2") (pin "1") (pinfunction "1_1") (pintype "bidirectional"))
      (node (ref "F3") (pin "1") (pinfunction "1_1") (pintype "bidirectional"))
      (node (ref "JP1") (pin "2") (pinfunction "2_2") (pintype "passive"))
      (node (ref "P1") (pin "3V3") (pinfunction "3V3_3V3") (pintype "bidirectional"))
      (node (ref "R3") (pin "2") (pinfunction "2_2") (pintype "passive"))
      (node (ref "R4") (pin "2") (pinfunction "2_2") (pintype "passive"))
      (node (ref "R5") (pin "2") (pinfunction "2_2") (pintype "passive"))
      (node (ref "R6") (pin "2") (pinfunction "2_2") (pintype "passive"))
      (node (ref "U1") (pin "2") (pinfunction "+VS_2") (pintype "power_in"))
      (node (ref "U1") (pin "4") (pinfunction "~{SHTDWN}_4") (pintype "passive"))
      (node (ref "U2") (pin "8") (pinfunction "VDD_8") (pintype "power_in"))
      (node (ref "U8") (pin "8") (pinfunction "VCC_8") (pintype "power_in"))
    )
    (net (code "40") (name "VCC-EXT") (class "Default")
      (node (ref "F3") (pin "2") (pinfunction "2_2") (pintype "bidirectional"))
      (node (ref "J1") (pin "3") (pinfunction "3_3") (pintype "bidirectional"))
      (node (ref "J2") (pin "5") (pinfunction "5_5") (pintype "bidirectional"))
      (node (ref "J3") (pin "3") (pinfunction "3_3") (pintype "bidirectional"))
      (node (ref "V3") (pin "2") (pinfunction "2_2") (pintype "passive"))
    )
    (net (code "41") (name "VCC2-EXT") (class "Default")
      (node (ref "F2") (pin "2") (pinfunction "2_2") (pintype "bidirectional"))
      (node (ref "J6") (pin "3") (pinfunction "3_3") (pintype "bidirectional"))
      (node (ref "J7") (pin "6") (pinfunction "6_6") (pintype "passive"))
      (node (ref "V2") (pin "2") (pinfunction "2_2") (pintype "passive"))
    )
    (net (code "42") (name "VDD") (class "Default")
      (node (ref "JP1") (pin "1") (pinfunction "1_1") (pintype "passive"))
      (node (ref "U3") (pin "1") (pinfunction "VDD_1") (pintype "power_in"))
    )
    (net (code "43") (name "VUSB") (class "Default")
      (node (ref "C8") (pin "P$1") (pinfunction "P$1_P$1") (pintype "passive"))
      (node (ref "F1") (pin "2") (pinfunction "2_2") (pintype "bidirectional"))
      (node (ref "P1") (pin "VUSB") (pinfunction "VUSB_VUSB") (pintype "bidirectional"))
      (node (ref "V1") (pin "2") (pinfunction "2_2") (pintype "passive"))
    )
    (net (code "44") (name "WAKE") (class "Default")
      (node (ref "P1") (pin "D8") (pinfunction "D8_D8") (pintype "bidirectional"))
      (node (ref "U3") (pin "5") (pinfunction "WAKE_5") (pintype "bidirectional"))
    )
    (net (code "45") (name "unconnected-(J4-PAD1-PadNC1)") (class "Default")
      (node (ref "J4") (pin "NC1") (pinfunction "PAD1_NC1") (pintype "bidirectional"))
    )
    (net (code "46") (name "unconnected-(J4-PAD2-PadNC2)") (class "Default")
      (node (ref "J4") (pin "NC2") (pinfunction "PAD2_NC2") (pintype "bidirectional"))
    )
    (net (code "47") (name "unconnected-(J5-PAD1-PadNC1)") (class "Default")
      (node (ref "J5") (pin "NC1") (pinfunction "PAD1_NC1") (pintype "bidirectional"))
    )
    (net (code "48") (name "unconnected-(J5-PAD2-PadNC2)") (class "Default")
      (node (ref "J5") (pin "NC2") (pinfunction "PAD2_NC2") (pintype "bidirectional"))
    )
    (net (code "49") (name "unconnected-(P1-PadD5)") (class "Default")
      (node (ref "P1") (pin "D5") (pinfunction "D5_D5") (pintype "bidirectional"))
    )
    (net (code "50") (name "unconnected-(P1-PadD7)") (class "Default")
      (node (ref "P1") (pin "D7") (pinfunction "D7_D7") (pintype "bidirectional"))
    )
    (net (code "51") (name "unconnected-(P1-PadNC)") (class "Default")
      (node (ref "P1") (pin "NC") (pinfunction "NC_NC") (pintype "bidirectional"))
    )
    (net (code "52") (name "unconnected-(U1-NC-Pad3)") (class "Default")
      (node (ref "U1") (pin "3") (pinfunction "NC_3") (pintype "passive"))
    )
    (net (code "53") (name "unconnected-(U7-Q-Pad5)") (class "Default")
      (node (ref "U7") (pin "5") (pinfunction "Q_5") (pintype "output"))
    )
    (net (code "54") (name "~{RST}") (class "Default")
      (node (ref "P1") (pin "RST") (pinfunction "~{RST}_RST") (pintype "bidirectional"))
      (node (ref "R3") (pin "1") (pinfunction "1_1") (pintype "passive"))
      (node (ref "U3") (pin "6") (pinfunction "~{RST}_6") (pintype "bidirectional"))
    )
  )
)
